# D1.net
KiCad netlist of a schematic drawn in EAGLE
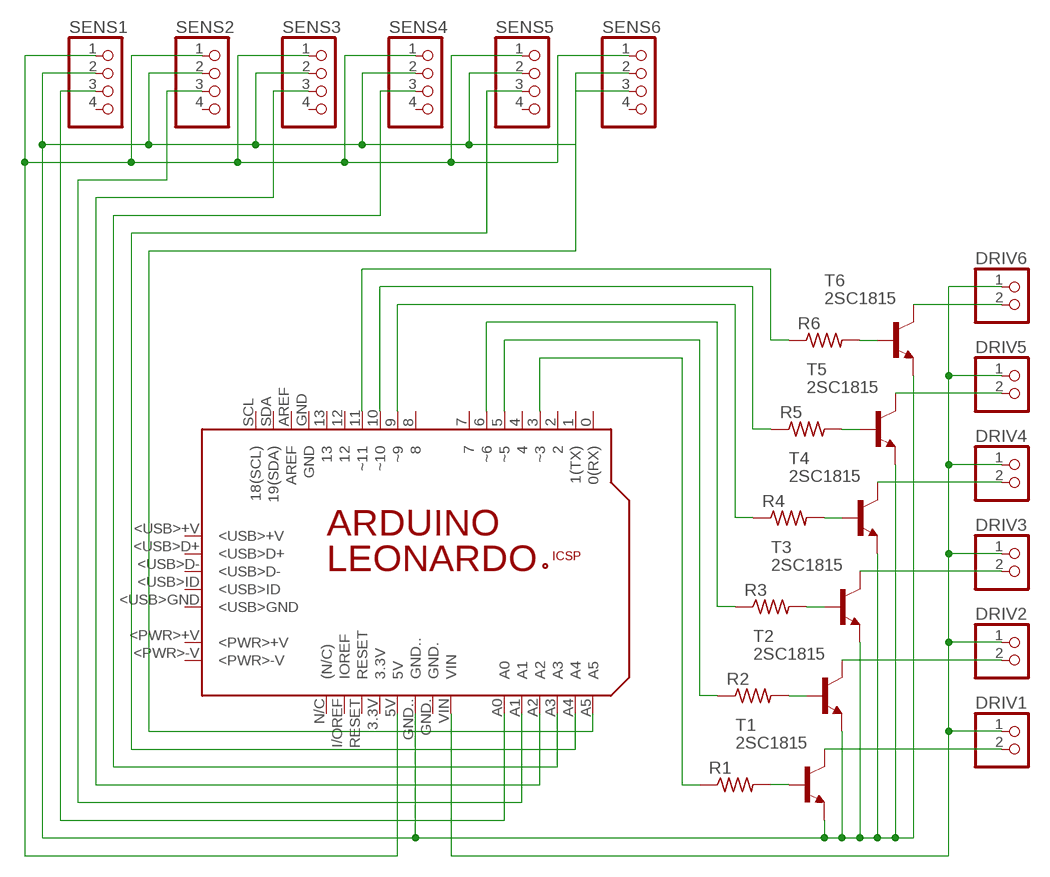
[diagram p0: schematic, sheet 1]

(export (version "E")
  (design (tool "Eeschema 10.0.6"))
  (components
    (comp (ref "DRIV1")
      (value "PINHD-1X2")
      (footprint "eagle-import:1X02")
      (libsource (lib "eagle-import") (part "PINHD-1X2"))
    )
    (comp (ref "DRIV2")
      (value "PINHD-1X2")
      (footprint "eagle-import:1X02")
      (libsource (lib "eagle-import") (part "PINHD-1X2"))
    )
    (comp (ref "DRIV3")
      (value "PINHD-1X2")
      (footprint "eagle-import:1X02")
      (libsource (lib "eagle-import") (part "PINHD-1X2"))
    )
    (comp (ref "DRIV4")
      (value "PINHD-1X2")
      (footprint "eagle-import:1X02")
      (libsource (lib "eagle-import") (part "PINHD-1X2"))
    )
    (comp (ref "DRIV5")
      (value "PINHD-1X2")
      (footprint "eagle-import:1X02")
      (libsource (lib "eagle-import") (part "PINHD-1X2"))
    )
    (comp (ref "DRIV6")
      (value "PINHD-1X2")
      (footprint "eagle-import:1X02")
      (libsource (lib "eagle-import") (part "PINHD-1X2"))
    )
    (comp (ref "PCB2")
      (value "ARDUINO_LEONARDO")
      (footprint "eagle-import:ARDUINO_LEONARDO")
      (libsource (lib "eagle-import") (part "ARDUINO_LEONARDO"))
    )
    (comp (ref "R1")
      (value "R-US_0204/5")
      (footprint "eagle-import:0204_5")
      (libsource (lib "eagle-import") (part "R-US_0204/5"))
    )
    (comp (ref "R2")
      (value "R-US_0204/5")
      (footprint "eagle-import:0204_5")
      (libsource (lib "eagle-import") (part "R-US_0204/5"))
    )
    (comp (ref "R3")
      (value "R-US_0204/5")
      (footprint "eagle-import:0204_5")
      (libsource (lib "eagle-import") (part "R-US_0204/5"))
    )
    (comp (ref "R4")
      (value "R-US_0204/5")
      (footprint "eagle-import:0204_5")
      (libsource (lib "eagle-import") (part "R-US_0204/5"))
    )
    (comp (ref "R5")
      (value "R-US_0204/5")
      (footprint "eagle-import:0204_5")
      (libsource (lib "eagle-import") (part "R-US_0204/5"))
    )
    (comp (ref "R6")
      (value "R-US_0204/5")
      (footprint "eagle-import:0204_5")
      (libsource (lib "eagle-import") (part "R-US_0204/5"))
    )
    (comp (ref "SENS1")
      (value "PINHD-1X4")
      (footprint "eagle-import:1X04")
      (libsource (lib "eagle-import") (part "PINHD-1X4"))
    )
    (comp (ref "SENS2")
      (value "PINHD-1X4")
      (footprint "eagle-import:1X04")
      (libsource (lib "eagle-import") (part "PINHD-1X4"))
    )
    (comp (ref "SENS3")
      (value "PINHD-1X4")
      (footprint "eagle-import:1X04")
      (libsource (lib "eagle-import") (part "PINHD-1X4"))
    )
    (comp (ref "SENS4")
      (value "PINHD-1X4")
      (footprint "eagle-import:1X04")
      (libsource (lib "eagle-import") (part "PINHD-1X4"))
    )
    (comp (ref "SENS5")
      (value "PINHD-1X4")
      (footprint "eagle-import:1X04")
      (libsource (lib "eagle-import") (part "PINHD-1X4"))
    )
    (comp (ref "SENS6")
      (value "PINHD-1X4")
      (footprint "eagle-import:1X04")
      (libsource (lib "eagle-import") (part "PINHD-1X4"))
    )
    (comp (ref "T1")
      (value "2SC1815")
      (footprint "eagle-import:TO92-ECB")
      (libsource (lib "eagle-import") (part "2SC1815"))
    )
    (comp (ref "T2")
      (value "2SC1815")
      (footprint "eagle-import:TO92-ECB")
      (libsource (lib "eagle-import") (part "2SC1815"))
    )
    (comp (ref "T3")
      (value "2SC1815")
      (footprint "eagle-import:TO92-ECB")
      (libsource (lib "eagle-import") (part "2SC1815"))
    )
    (comp (ref "T4")
      (value "2SC1815")
      (footprint "eagle-import:TO92-ECB")
      (libsource (lib "eagle-import") (part "2SC1815"))
    )
    (comp (ref "T5")
      (value "2SC1815")
      (footprint "eagle-import:TO92-ECB")
      (libsource (lib "eagle-import") (part "2SC1815"))
    )
    (comp (ref "T6")
      (value "2SC1815")
      (footprint "eagle-import:TO92-ECB")
      (libsource (lib "eagle-import") (part "2SC1815"))
    )
  )
  (nets
    (net (code "1") (name "Net-(DRIV1-Pad1)") (class "Default")
      (node (ref "DRIV1") (pin "1") (pinfunction "1_1") (pintype "passive"))
      (node (ref "DRIV2") (pin "1") (pinfunction "1_1") (pintype "passive"))
      (node (ref "DRIV3") (pin "1") (pinfunction "1_1") (pintype "passive"))
      (node (ref "DRIV4") (pin "1") (pinfunction "1_1") (pintype "passive"))
      (node (ref "DRIV5") (pin "1") (pinfunction "1_1") (pintype "passive"))
      (node (ref "DRIV6") (pin "1") (pinfunction "1_1") (pintype "passive"))
      (node (ref "PCB2") (pin "VIN") (pinfunction "VIN_VIN") (pintype "bidirectional"))
    )
    (net (code "2") (name "Net-(DRIV1-Pad2)") (class "Default")
      (node (ref "DRIV1") (pin "2") (pinfunction "2_2") (pintype "passive"))
      (node (ref "T1") (pin "C") (pinfunction "C_C") (pintype "passive"))
    )
    (net (code "3") (name "Net-(DRIV2-Pad2)") (class "Default")
      (node (ref "DRIV2") (pin "2") (pinfunction "2_2") (pintype "passive"))
      (node (ref "T2") (pin "C") (pinfunction "C_C") (pintype "passive"))
    )
    (net (code "4") (name "Net-(DRIV3-Pad2)") (class "Default")
      (node (ref "DRIV3") (pin "2") (pinfunction "2_2") (pintype "passive"))
      (node (ref "T3") (pin "C") (pinfunction "C_C") (pintype "passive"))
    )
    (net (code "5") (name "Net-(DRIV4-Pad2)") (class "Default")
      (node (ref "DRIV4") (pin "2") (pinfunction "2_2") (pintype "passive"))
      (node (ref "T4") (pin "C") (pinfunction "C_C") (pintype "passive"))
    )
    (net (code "6") (name "Net-(DRIV5-Pad2)") (class "Default")
      (node (ref "DRIV5") (pin "2") (pinfunction "2_2") (pintype "passive"))
      (node (ref "T5") (pin "C") (pinfunction "C_C") (pintype "passive"))
    )
    (net (code "7") (name "Net-(DRIV6-Pad2)") (class "Default")
      (node (ref "DRIV6") (pin "2") (pinfunction "2_2") (pintype "passive"))
      (node (ref "T6") (pin "C") (pinfunction "C_C") (pintype "passive"))
    )
    (net (code "8") (name "Net-(PCB2-Pad5V)") (class "Default")
      (node (ref "PCB2") (pin "5V") (pinfunction "5V_5V") (pintype "bidirectional"))
      (node (ref "SENS1") (pin "1") (pinfunction "1_1") (pintype "passive"))
      (node (ref "SENS2") (pin "1") (pinfunction "1_1") (pintype "passive"))
      (node (ref "SENS3") (pin "1") (pinfunction "1_1") (pintype "passive"))
      (node (ref "SENS4") (pin "1") (pinfunction "1_1") (pintype "passive"))
      (node (ref "SENS5") (pin "1") (pinfunction "1_1") (pintype "passive"))
      (node (ref "SENS6") (pin "1") (pinfunction "1_1") (pintype "passive"))
    )
    (net (code "9") (name "Net-(PCB2-PadA0)") (class "Default")
      (node (ref "PCB2") (pin "A0") (pinfunction "A0_A0") (pintype "bidirectional"))
      (node (ref "SENS1") (pin "3") (pinfunction "3_3") (pintype "passive"))
    )
    (net (code "10") (name "Net-(PCB2-PadA1)") (class "Default")
      (node (ref "PCB2") (pin "A1") (pinfunction "A1_A1") (pintype "bidirectional"))
      (node (ref "SENS2") (pin "3") (pinfunction "3_3") (pintype "passive"))
    )
    (net (code "11") (name "Net-(PCB2-PadA2)") (class "Default")
      (node (ref "PCB2") (pin "A2") (pinfunction "A2_A2") (pintype "bidirectional"))
      (node (ref "SENS3") (pin "3") (pinfunction "3_3") (pintype "passive"))
    )
    (net (code "12") (name "Net-(PCB2-PadA3)") (class "Default")
      (node (ref "PCB2") (pin "A3") (pinfunction "A3_A3") (pintype "bidirectional"))
      (node (ref "SENS4") (pin "3") (pinfunction "3_3") (pintype "passive"))
    )
    (net (code "13") (name "Net-(PCB2-PadA4)") (class "Default")
      (node (ref "PCB2") (pin "A4") (pinfunction "A4_A4") (pintype "bidirectional"))
      (node (ref "SENS5") (pin "3") (pinfunction "3_3") (pintype "passive"))
    )
    (net (code "14") (name "Net-(PCB2-PadA5)") (class "Default")
      (node (ref "PCB2") (pin "A5") (pinfunction "A5_A5") (pintype "bidirectional"))
      (node (ref "SENS6") (pin "3") (pinfunction "3_3") (pintype "passive"))
    )
    (net (code "15") (name "Net-(PCB2-PadGND..)") (class "Default")
      (node (ref "PCB2") (pin "GND..") (pinfunction "GND.._GND..") (pintype "bidirectional"))
      (node (ref "SENS1") (pin "2") (pinfunction "2_2") (pintype "passive"))
      (node (ref "SENS2") (pin "2") (pinfunction "2_2") (pintype "passive"))
      (node (ref "SENS3") (pin "2") (pinfunction "2_2") (pintype "passive"))
      (node (ref "SENS4") (pin "2") (pinfunction "2_2") (pintype "passive"))
      (node (ref "SENS5") (pin "2") (pinfunction "2_2") (pintype "passive"))
      (node (ref "SENS6") (pin "2") (pinfunction "2_2") (pintype "passive"))
      (node (ref "T1") (pin "E") (pinfunction "E_E") (pintype "passive"))
      (node (ref "T2") (pin "E") (pinfunction "E_E") (pintype "passive"))
      (node (ref "T3") (pin "E") (pinfunction "E_E") (pintype "passive"))
      (node (ref "T4") (pin "E") (pinfunction "E_E") (pintype "passive"))
      (node (ref "T5") (pin "E") (pinfunction "E_E") (pintype "passive"))
      (node (ref "T6") (pin "E") (pinfunction "E_E") (pintype "passive"))
    )
    (net (code "16") (name "Net-(PCB2-~{3})") (class "Default")
      (node (ref "PCB2") (pin "3") (pinfunction "~{3}_3") (pintype "bidirectional"))
      (node (ref "R1") (pin "1") (pinfunction "1_1") (pintype "passive"))
    )
    (net (code "17") (name "Net-(PCB2-~{5})") (class "Default")
      (node (ref "PCB2") (pin "5") (pinfunction "~{5}_5") (pintype "bidirectional"))
      (node (ref "R2") (pin "1") (pinfunction "1_1") (pintype "passive"))
    )
    (net (code "18") (name "Net-(PCB2-~{6})") (class "Default")
      (node (ref "PCB2") (pin "6") (pinfunction "~{6}_6") (pintype "bidirectional"))
      (node (ref "R3") (pin "1") (pinfunction "1_1") (pintype "passive"))
    )
    (net (code "19") (name "Net-(PCB2-~{9})") (class "Default")
      (node (ref "PCB2") (pin "9") (pinfunction "~{9}_9") (pintype "bidirectional"))
      (node (ref "R4") (pin "1") (pinfunction "1_1") (pintype "passive"))
    )
    (net (code "20") (name "Net-(PCB2-~{10})") (class "Default")
      (node (ref "PCB2") (pin "10") (pinfunction "~{10}_10") (pintype "bidirectional"))
      (node (ref "R5") (pin "1") (pinfunction "1_1") (pintype "passive"))
    )
    (net (code "21") (name "Net-(PCB2-~{11})") (class "Default")
      (node (ref "PCB2") (pin "11") (pinfunction "~{11}_11") (pintype "bidirectional"))
      (node (ref "R6") (pin "1") (pinfunction "1_1") (pintype "passive"))
    )
    (net (code "22") (name "Net-(R1-Pad2)") (class "Default")
      (node (ref "R1") (pin "2") (pinfunction "2_2") (pintype "passive"))
      (node (ref "T1") (pin "B") (pinfunction "B_B") (pintype "passive"))
    )
    (net (code "23") (name "Net-(R2-Pad2)") (class "Default")
      (node (ref "R2") (pin "2") (pinfunction "2_2") (pintype "passive"))
      (node (ref "T2") (pin "B") (pinfunction "B_B") (pintype "passive"))
    )
    (net (code "24") (name "Net-(R3-Pad2)") (class "Default")
      (node (ref "R3") (pin "2") (pinfunction "2_2") (pintype "passive"))
      (node (ref "T3") (pin "B") (pinfunction "B_B") (pintype "passive"))
    )
    (net (code "25") (name "Net-(R4-Pad2)") (class "Default")
      (node (ref "R4") (pin "2") (pinfunction "2_2") (pintype "passive"))
      (node (ref "T4") (pin "B") (pinfunction "B_B") (pintype "passive"))
    )
    (net (code "26") (name "Net-(R5-Pad2)") (class "Default")
      (node (ref "R5") (pin "2") (pinfunction "2_2") (pintype "passive"))
      (node (ref "T5") (pin "B") (pinfunction "B_B") (pintype "passive"))
    )
    (net (code "27") (name "Net-(R6-Pad2)") (class "Default")
      (node (ref "R6") (pin "2") (pinfunction "2_2") (pintype "passive"))
      (node (ref "T6") (pin "B") (pinfunction "B_B") (pintype "passive"))
    )
    (net (code "28") (name "unconnected-(PCB2-(N{slash}C)-PadN{slash}C)") (class "Default")
      (node (ref "PCB2") (pin "N/C") (pinfunction "(N/C)_N/C") (pintype "bidirectional"))
    )
    (net (code "29") (name "unconnected-(PCB2-0(RX)-Pad0)") (class "Default")
      (node (ref "PCB2") (pin "0") (pinfunction "0(RX)_0") (pintype "bidirectional"))
    )
    (net (code "30") (name "unconnected-(PCB2-1(TX)-Pad1)") (class "Default")
      (node (ref "PCB2") (pin "1") (pinfunction "1(TX)_1") (pintype "bidirectional"))
    )
    (net (code "31") (name "unconnected-(PCB2-18(SCL)-PadSCL)") (class "Default")
      (node (ref "PCB2") (pin "SCL") (pinfunction "18(SCL)_SCL") (pintype "bidirectional"))
    )
    (net (code "32") (name "unconnected-(PCB2-19(SDA)-PadSDA)") (class "Default")
      (node (ref "PCB2") (pin "SDA") (pinfunction "19(SDA)_SDA") (pintype "bidirectional"))
    )
    (net (code "33") (name "unconnected-(PCB2-IOREF-PadI{slash}OREF)") (class "Default")
      (node (ref "PCB2") (pin "I/OREF") (pinfunction "IOREF_I/OREF") (pintype "bidirectional"))
    )
    (net (code "34") (name "unconnected-(PCB2-Pad+5V)") (class "Default")
      (node (ref "PCB2") (pin "+5V") (pinfunction "+5V_+5V") (pintype "bidirectional"))
    )
    (net (code "35") (name "unconnected-(PCB2-Pad2)") (class "Default")
      (node (ref "PCB2") (pin "2") (pinfunction "2_2") (pintype "bidirectional"))
    )
    (net (code "36") (name "unconnected-(PCB2-Pad3.3V)") (class "Default")
      (node (ref "PCB2") (pin "3.3V") (pinfunction "3.3V_3.3V") (pintype "bidirectional"))
    )
    (net (code "37") (name "unconnected-(PCB2-Pad4)") (class "Default")
      (node (ref "PCB2") (pin "4") (pinfunction "4_4") (pintype "bidirectional"))
    )
    (net (code "38") (name "unconnected-(PCB2-Pad7)") (class "Default")
      (node (ref "PCB2") (pin "7") (pinfunction "7_7") (pintype "bidirectional"))
    )
    (net (code "39") (name "unconnected-(PCB2-Pad8)") (class "Default")
      (node (ref "PCB2") (pin "8") (pinfunction "8_8") (pintype "bidirectional"))
    )
    (net (code "40") (name "unconnected-(PCB2-Pad12)") (class "Default")
      (node (ref "PCB2") (pin "12") (pinfunction "12_12") (pintype "bidirectional"))
    )
    (net (code "41") (name "unconnected-(PCB2-Pad13)") (class "Default")
      (node (ref "PCB2") (pin "13") (pinfunction "13_13") (pintype "bidirectional"))
    )
    (net (code "42") (name "unconnected-(PCB2-Pad<PWR>+V)") (class "Default")
      (node (ref "PCB2") (pin "<PWR>+V") (pinfunction "<PWR>+V_<PWR>+V") (pintype "bidirectional"))
    )
    (net (code "43") (name "unconnected-(PCB2-Pad<PWR>-V)") (class "Default")
      (node (ref "PCB2") (pin "<PWR>-V") (pinfunction "<PWR>-V_<PWR>-V") (pintype "bidirectional"))
    )
    (net (code "44") (name "unconnected-(PCB2-Pad<USB>+V)") (class "Default")
      (node (ref "PCB2") (pin "<USB>+V") (pinfunction "<USB>+V_<USB>+V") (pintype "bidirectional"))
    )
    (net (code "45") (name "unconnected-(PCB2-Pad<USB>D+)") (class "Default")
      (node (ref "PCB2") (pin "<USB>D+") (pinfunction "<USB>D+_<USB>D+") (pintype "bidirectional"))
    )
    (net (code "46") (name "unconnected-(PCB2-Pad<USB>D-)") (class "Default")
      (node (ref "PCB2") (pin "<USB>D-") (pinfunction "<USB>D-_<USB>D-") (pintype "bidirectional"))
    )
    (net (code "47") (name "unconnected-(PCB2-Pad<USB>GND)") (class "Default")
      (node (ref "PCB2") (pin "<USB>GND") (pinfunction "<USB>GND_<USB>GND") (pintype "bidirectional"))
    )
    (net (code "48") (name "unconnected-(PCB2-Pad<USB>ID)") (class "Default")
      (node (ref "PCB2") (pin "<USB>ID") (pinfunction "<USB>ID_<USB>ID") (pintype "bidirectional"))
    )
    (net (code "49") (name "unconnected-(PCB2-PadAREF)") (class "Default")
      (node (ref "PCB2") (pin "AREF") (pinfunction "AREF_AREF") (pintype "bidirectional"))
    )
    (net (code "50") (name "unconnected-(PCB2-PadGND)") (class "Default")
      (node (ref "PCB2") (pin "GND") (pinfunction "GND_GND") (pintype "bidirectional"))
    )
    (net (code "51") (name "unconnected-(PCB2-PadGND.)") (class "Default")
      (node (ref "PCB2") (pin "GND.") (pinfunction "GND._GND.") (pintype "bidirectional"))
    )
    (net (code "52") (name "unconnected-(PCB2-PadGND_)") (class "Default")
      (node (ref "PCB2") (pin "GND_") (pinfunction "GND__GND_") (pintype "bidirectional"))
    )
    (net (code "53") (name "unconnected-(PCB2-PadMISO)") (class "Default")
      (node (ref "PCB2") (pin "MISO") (pinfunction "MISO_MISO") (pintype "bidirectional"))
    )
    (net (code "54") (name "unconnected-(PCB2-PadMOSI)") (class "Default")
      (node (ref "PCB2") (pin "MOSI") (pinfunction "MOSI_MOSI") (pintype "bidirectional"))
    )
    (net (code "55") (name "unconnected-(PCB2-PadRESET)") (class "Default")
      (node (ref "PCB2") (pin "RESET") (pinfunction "RESET_RESET") (pintype "bidirectional"))
    )
    (net (code "56") (name "unconnected-(PCB2-PadRESET.)") (class "Default")
      (node (ref "PCB2") (pin "RESET.") (pinfunction "RESET._RESET.") (pintype "bidirectional"))
    )
    (net (code "57") (name "unconnected-(PCB2-PadSCK)") (class "Default")
      (node (ref "PCB2") (pin "SCK") (pinfunction "SCK_SCK") (pintype "bidirectional"))
    )
    (net (code "58") (name "unconnected-(SENS1-Pad4)") (class "Default")
      (node (ref "SENS1") (pin "4") (pinfunction "4_4") (pintype "passive"))
    )
    (net (code "59") (name "unconnected-(SENS2-Pad4)") (class "Default")
      (node (ref "SENS2") (pin "4") (pinfunction "4_4") (pintype "passive"))
    )
    (net (code "60") (name "unconnected-(SENS3-Pad4)") (class "Default")
      (node (ref "SENS3") (pin "4") (pinfunction "4_4") (pintype "passive"))
    )
    (net (code "61") (name "unconnected-(SENS4-Pad4)") (class "Default")
      (node (ref "SENS4") (pin "4") (pinfunction "4_4") (pintype "passive"))
    )
    (net (code "62") (name "unconnected-(SENS5-Pad4)") (class "Default")
      (node (ref "SENS5") (pin "4") (pinfunction "4_4") (pintype "passive"))
    )
    (net (code "63") (name "unconnected-(SENS6-Pad4)") (class "Default")
      (node (ref "SENS6") (pin "4") (pinfunction "4_4") (pintype "passive"))
    )
  )
)
